# design.net
KiCad netlist of a schematic drawn in Altium Designer
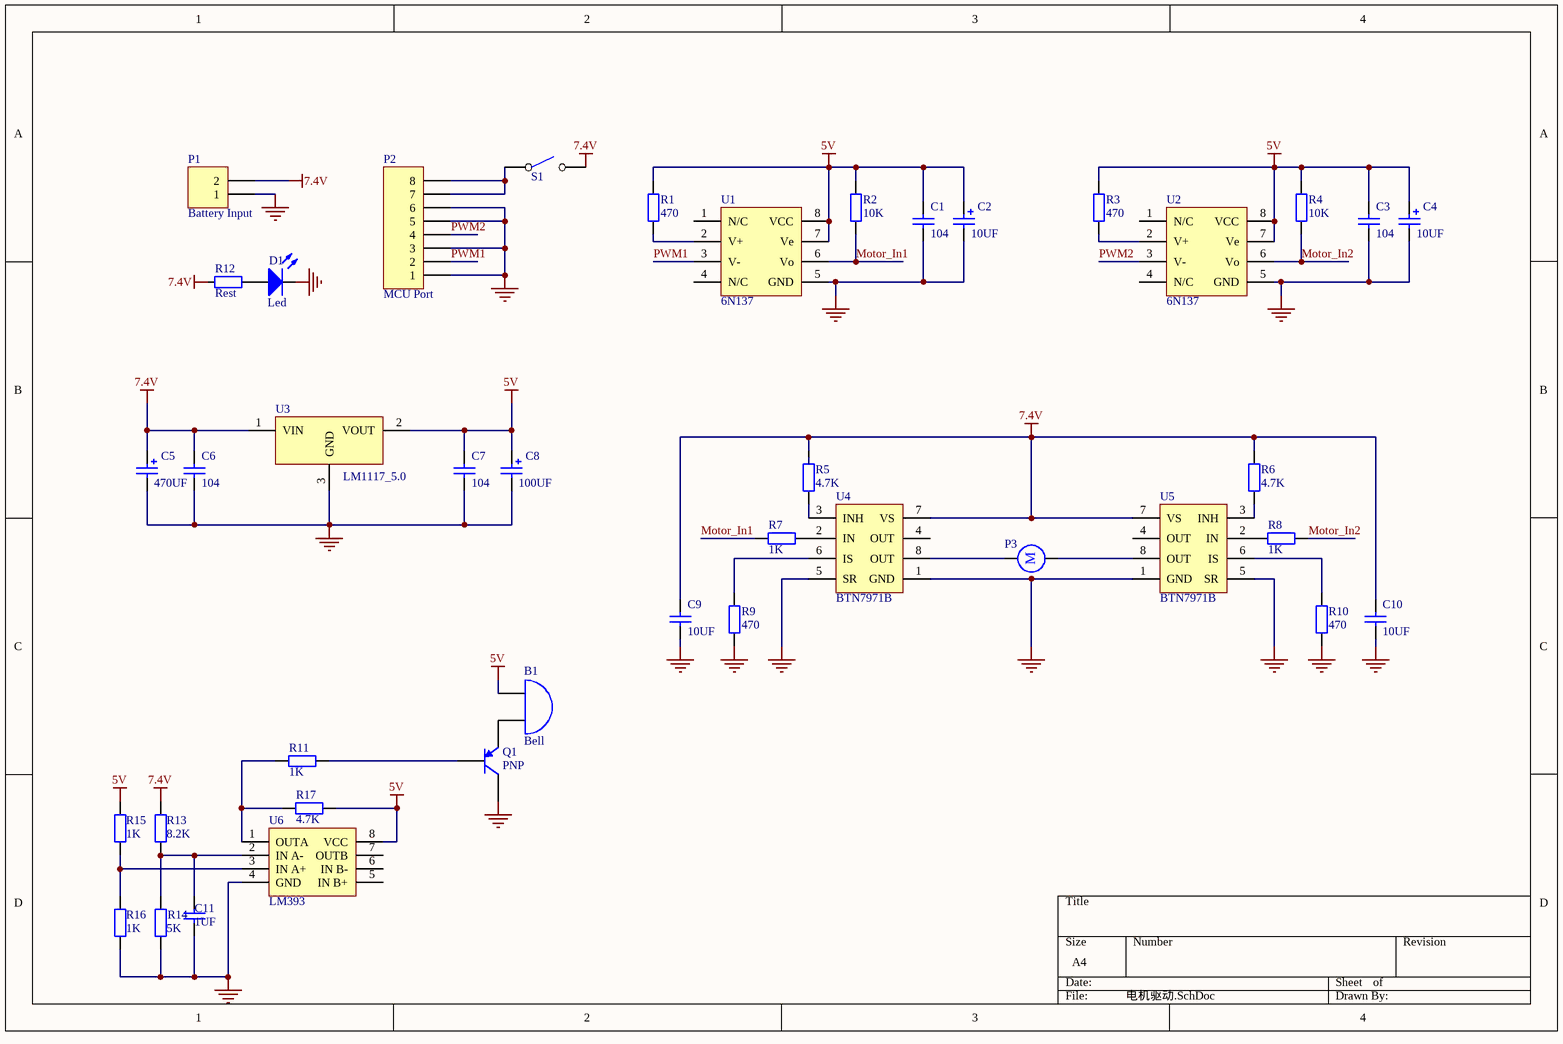
[diagram p0: 电机驱动.SchDoc]

(export (version "E")
  (design (tool "Eeschema 10.0.6"))
  (components
    (comp (ref "B1")
      (value "Bell")
      (footprint "Buzzer")
      (description "Electrical Bell")
      (fields (field (name "PUBLISHER") "Altium Limited"))
      (libsource (lib "Miscellaneous Devices") (part "Bell"))
    )
    (comp (ref "C1") (value "104") (footprint "0805") (libsource (lib "飞思卡尔") (part "Cap")))
    (comp (ref "C2")
      (value "10UF")
      (footprint "tiepian 100uf 6*7")
      (libsource (lib "飞思卡尔") (part "Cap Pol1"))
    )
    (comp (ref "C3") (value "104") (footprint "0805") (libsource (lib "飞思卡尔") (part "Cap")))
    (comp (ref "C4")
      (value "10UF")
      (footprint "tiepian 100uf 6*7")
      (libsource (lib "飞思卡尔") (part "Cap Pol1"))
    )
    (comp (ref "C5")
      (value "470UF")
      (footprint "tie pian 470uf 10*10.3")
      (libsource (lib "飞思卡尔") (part "Cap Pol1"))
    )
    (comp (ref "C6") (value "104") (footprint "0805") (libsource (lib "飞思卡尔") (part "Cap")))
    (comp (ref "C7") (value "104") (footprint "0805") (libsource (lib "飞思卡尔") (part "Cap")))
    (comp (ref "C8")
      (value "100UF")
      (footprint "tiepian 100uf 6*7")
      (libsource (lib "飞思卡尔") (part "Cap Pol1"))
    )
    (comp (ref "C9") (value "10UF") (footprint "7343") (libsource (lib "飞思卡尔") (part "Cap")))
    (comp (ref "C10") (value "10UF") (footprint "7343") (libsource (lib "飞思卡尔") (part "Cap")))
    (comp (ref "C11") (value "1UF") (footprint "0805") (libsource (lib "飞思卡尔") (part "Cap")))
    (comp (ref "D1") (value "Led") (footprint "0805") (libsource (lib "飞思卡尔") (part "Led")))
    (comp (ref "P1")
      (value "Battery Input")
      (footprint "XT-30")
      (description "Header, 2-Pin")
      (fields (field (name "PUBLISHER") "Altium Limited"))
      (libsource (lib "Miscellaneous Connectors") (part "Header 2"))
    )
    (comp (ref "P2")
      (value "MCU Port")
      (footprint "8P-2.54")
      (description "Header, 8-Pin")
      (fields (field (name "PUBLISHER") "Altium Limited"))
      (libsource (lib "Miscellaneous Connectors") (part "Header 8"))
    )
    (comp (ref "P3") (value "Motor") (footprint "接头10MM") (libsource (lib "飞思卡尔") (part "Motor")))
    (comp (ref "Q1")
      (value "PNP")
      (footprint "SOT-23")
      (description "PNP Bipolar Transistor")
      (fields (field (name "PUBLISHER") "Altium Limited"))
      (libsource (lib "Miscellaneous Devices") (part "PNP"))
    )
    (comp (ref "R1") (value "470") (footprint "0805") (libsource (lib "") (part "Rest_1")))
    (comp (ref "R2") (value "10K") (footprint "0805") (libsource (lib "") (part "Rest_1")))
    (comp (ref "R3") (value "470") (footprint "0805") (libsource (lib "") (part "Rest_1")))
    (comp (ref "R4") (value "10K") (footprint "0805") (libsource (lib "") (part "Rest_1")))
    (comp (ref "R5") (value "4.7K") (footprint "0805") (libsource (lib "") (part "Rest_1")))
    (comp (ref "R6") (value "4.7K") (footprint "0805") (libsource (lib "") (part "Rest_1")))
    (comp (ref "R7") (value "1K") (footprint "0805") (libsource (lib "飞思卡尔") (part "Rest")))
    (comp (ref "R8") (value "1K") (footprint "0805") (libsource (lib "飞思卡尔") (part "Rest")))
    (comp (ref "R9") (value "470") (footprint "0805") (libsource (lib "") (part "Rest_1")))
    (comp (ref "R10") (value "470") (footprint "0805") (libsource (lib "") (part "Rest_1")))
    (comp (ref "R11") (value "1K") (footprint "0805") (libsource (lib "飞思卡尔") (part "Rest")))
    (comp (ref "R12") (value "Rest") (footprint "0805") (libsource (lib "") (part "Rest_2")))
    (comp (ref "R13") (value "8.2K") (footprint "0805") (libsource (lib "") (part "Rest_1")))
    (comp (ref "R14") (value "5K") (footprint "0805") (libsource (lib "") (part "Rest_1")))
    (comp (ref "R15") (value "1K") (footprint "0805") (libsource (lib "") (part "Rest_1")))
    (comp (ref "R16") (value "1K") (footprint "0805") (libsource (lib "") (part "Rest_1")))
    (comp (ref "R17") (value "4.7K") (footprint "0805") (libsource (lib "飞思卡尔") (part "Rest")))
    (comp (ref "S1") (value "单刀开关") (footprint "钮子开关") (libsource (lib "按钮&开关") (part "单刀开关")))
    (comp (ref "U1") (value "6N137") (footprint "6N137") (libsource (lib "飞思卡尔") (part "6n137")))
    (comp (ref "U2") (value "6N137") (footprint "6N137") (libsource (lib "飞思卡尔") (part "6n137")))
    (comp (ref "U3") (value "LM1117_5.0") (footprint "SOT-223") (libsource (lib "飞思卡尔") (part "LM1117_5V")))
    (comp (ref "U4") (value "BTN7971B") (footprint "BTN7971B") (libsource (lib "飞思卡尔") (part "BTN7971B")))
    (comp (ref "U5") (value "BTN7971B") (footprint "BTN7971B") (libsource (lib "") (part "BTN7971B_1")))
    (comp (ref "U6") (value "LM393") (footprint "SOP-8") (libsource (lib "飞思卡尔") (part "LM393")))
  )
  (nets
    (net (code "1") (name "/Motor_In1") (class "Default")
      (node (ref "R2") (pin "1") (pinfunction "1_1") (pintype "passive"))
      (node (ref "R7") (pin "2") (pinfunction "2_2") (pintype "passive"))
      (node (ref "U1") (pin "6") (pinfunction "Vo_6") (pintype "passive"))
    )
    (net (code "2") (name "/Motor_In2") (class "Default")
      (node (ref "R4") (pin "1") (pinfunction "1_1") (pintype "passive"))
      (node (ref "R8") (pin "1") (pinfunction "1_1") (pintype "passive"))
      (node (ref "U2") (pin "6") (pinfunction "Vo_6") (pintype "passive"))
    )
    (net (code "3") (name "/PWM1") (class "Default")
      (node (ref "P2") (pin "2") (pinfunction "2_2") (pintype "passive"))
      (node (ref "U1") (pin "3") (pinfunction "V-_3") (pintype "passive"))
    )
    (net (code "4") (name "/PWM2") (class "Default")
      (node (ref "P2") (pin "4") (pinfunction "4_4") (pintype "passive"))
      (node (ref "U2") (pin "3") (pinfunction "V-_3") (pintype "passive"))
    )
    (net (code "5") (name "5V") (class "Default")
      (node (ref "B1") (pin "1") (pinfunction "A_1") (pintype "passive"))
      (node (ref "C1") (pin "2") (pinfunction "2_2") (pintype "passive"))
      (node (ref "C2") (pin "1") (pinfunction "1_1") (pintype "passive"))
      (node (ref "C3") (pin "2") (pinfunction "2_2") (pintype "passive"))
      (node (ref "C4") (pin "1") (pinfunction "1_1") (pintype "passive"))
      (node (ref "C7") (pin "2") (pinfunction "2_2") (pintype "passive"))
      (node (ref "C8") (pin "1") (pinfunction "1_1") (pintype "passive"))
      (node (ref "R1") (pin "2") (pinfunction "2_2") (pintype "passive"))
      (node (ref "R15") (pin "2") (pinfunction "2_2") (pintype "passive"))
      (node (ref "R17") (pin "1") (pinfunction "1_1") (pintype "passive"))
      (node (ref "R2") (pin "2") (pinfunction "2_2") (pintype "passive"))
      (node (ref "R3") (pin "2") (pinfunction "2_2") (pintype "passive"))
      (node (ref "R4") (pin "2") (pinfunction "2_2") (pintype "passive"))
      (node (ref "U1") (pin "7") (pinfunction "Ve_7") (pintype "passive"))
      (node (ref "U1") (pin "8") (pinfunction "VCC_8") (pintype "passive"))
      (node (ref "U2") (pin "7") (pinfunction "Ve_7") (pintype "passive"))
      (node (ref "U2") (pin "8") (pinfunction "VCC_8") (pintype "passive"))
      (node (ref "U3") (pin "2") (pinfunction "VOUT_2") (pintype "passive"))
      (node (ref "U6") (pin "8") (pinfunction "VCC_8") (pintype "passive"))
    )
    (net (code "6") (name "7.4V") (class "Default")
      (node (ref "C10") (pin "2") (pinfunction "2_2") (pintype "passive"))
      (node (ref "C5") (pin "1") (pinfunction "1_1") (pintype "passive"))
      (node (ref "C6") (pin "2") (pinfunction "2_2") (pintype "passive"))
      (node (ref "C9") (pin "2") (pinfunction "2_2") (pintype "passive"))
      (node (ref "P1") (pin "2") (pinfunction "2_2") (pintype "passive"))
      (node (ref "R13") (pin "2") (pinfunction "2_2") (pintype "passive"))
      (node (ref "R5") (pin "2") (pinfunction "2_2") (pintype "passive"))
      (node (ref "R6") (pin "2") (pinfunction "2_2") (pintype "passive"))
      (node (ref "S1") (pin "2") (pinfunction "2_2") (pintype "passive"))
      (node (ref "U3") (pin "1") (pinfunction "VIN_1") (pintype "passive"))
      (node (ref "U4") (pin "7") (pinfunction "VS_7") (pintype "passive"))
      (node (ref "U5") (pin "7") (pinfunction "VS_7") (pintype "passive"))
    )
    (net (code "7") (name "GND") (class "Default")
      (node (ref "C1") (pin "1") (pinfunction "1_1") (pintype "passive"))
      (node (ref "C10") (pin "1") (pinfunction "1_1") (pintype "passive"))
      (node (ref "C11") (pin "1") (pinfunction "1_1") (pintype "passive"))
      (node (ref "C2") (pin "2") (pinfunction "2_2") (pintype "passive"))
      (node (ref "C3") (pin "1") (pinfunction "1_1") (pintype "passive"))
      (node (ref "C4") (pin "2") (pinfunction "2_2") (pintype "passive"))
      (node (ref "C5") (pin "2") (pinfunction "2_2") (pintype "passive"))
      (node (ref "C6") (pin "1") (pinfunction "1_1") (pintype "passive"))
      (node (ref "C7") (pin "1") (pinfunction "1_1") (pintype "passive"))
      (node (ref "C8") (pin "2") (pinfunction "2_2") (pintype "passive"))
      (node (ref "C9") (pin "1") (pinfunction "1_1") (pintype "passive"))
      (node (ref "D1") (pin "2") (pinfunction "2_2") (pintype "passive"))
      (node (ref "P1") (pin "1") (pinfunction "1_1") (pintype "passive"))
      (node (ref "P2") (pin "1") (pinfunction "1_1") (pintype "passive"))
      (node (ref "P2") (pin "3") (pinfunction "3_3") (pintype "passive"))
      (node (ref "P2") (pin "5") (pinfunction "5_5") (pintype "passive"))
      (node (ref "P2") (pin "6") (pinfunction "6_6") (pintype "passive"))
      (node (ref "Q1") (pin "1") (pinfunction "C_1") (pintype "passive"))
      (node (ref "R10") (pin "1") (pinfunction "1_1") (pintype "passive"))
      (node (ref "R14") (pin "1") (pinfunction "1_1") (pintype "passive"))
      (node (ref "R16") (pin "1") (pinfunction "1_1") (pintype "passive"))
      (node (ref "R9") (pin "1") (pinfunction "1_1") (pintype "passive"))
      (node (ref "U1") (pin "5") (pinfunction "GND_5") (pintype "passive"))
      (node (ref "U2") (pin "5") (pinfunction "GND_5") (pintype "passive"))
      (node (ref "U3") (pin "3") (pinfunction "GND_3") (pintype "passive"))
      (node (ref "U4") (pin "1") (pinfunction "GND_1") (pintype "passive"))
      (node (ref "U4") (pin "5") (pinfunction "SR_5") (pintype "passive"))
      (node (ref "U5") (pin "1") (pinfunction "GND_1") (pintype "passive"))
      (node (ref "U5") (pin "5") (pinfunction "SR_5") (pintype "passive"))
      (node (ref "U6") (pin "4") (pinfunction "GND_4") (pintype "passive"))
    )
    (net (code "8") (name "Net-(B1-B)") (class "Default")
      (node (ref "B1") (pin "2") (pinfunction "B_2") (pintype "passive"))
      (node (ref "Q1") (pin "3") (pinfunction "E_3") (pintype "passive"))
    )
    (net (code "9") (name "Net-(D1-Pad1)") (class "Default")
      (node (ref "D1") (pin "1") (pinfunction "1_1") (pintype "passive"))
      (node (ref "R12") (pin "2") (pinfunction "2_2") (pintype "passive"))
    )
    (net (code "10") (name "Net-(P2-Pad7)") (class "Default")
      (node (ref "P2") (pin "7") (pinfunction "7_7") (pintype "passive"))
      (node (ref "P2") (pin "8") (pinfunction "8_8") (pintype "passive"))
      (node (ref "S1") (pin "1") (pinfunction "1_1") (pintype "passive"))
    )
    (net (code "11") (name "Net-(P3-Pad1)") (class "Default")
      (node (ref "P3") (pin "1") (pinfunction "1_1") (pintype "passive"))
      (node (ref "U4") (pin "8") (pinfunction "OUT_8") (pintype "passive"))
    )
    (net (code "12") (name "Net-(P3-Pad2)") (class "Default")
      (node (ref "P3") (pin "2") (pinfunction "2_2") (pintype "passive"))
      (node (ref "U5") (pin "8") (pinfunction "OUT_8") (pintype "passive"))
    )
    (net (code "13") (name "Net-(Q1-B)") (class "Default")
      (node (ref "Q1") (pin "2") (pinfunction "B_2") (pintype "passive"))
      (node (ref "R11") (pin "1") (pinfunction "1_1") (pintype "passive"))
    )
    (net (code "14") (name "Net-(U1-V+)") (class "Default")
      (node (ref "R1") (pin "1") (pinfunction "1_1") (pintype "passive"))
      (node (ref "U1") (pin "2") (pinfunction "V+_2") (pintype "passive"))
    )
    (net (code "15") (name "Net-(U2-V+)") (class "Default")
      (node (ref "R3") (pin "1") (pinfunction "1_1") (pintype "passive"))
      (node (ref "U2") (pin "2") (pinfunction "V+_2") (pintype "passive"))
    )
    (net (code "16") (name "Net-(U4-IN)") (class "Default")
      (node (ref "R7") (pin "1") (pinfunction "1_1") (pintype "passive"))
      (node (ref "U4") (pin "2") (pinfunction "IN_2") (pintype "passive"))
    )
    (net (code "17") (name "Net-(U4-INH)") (class "Default")
      (node (ref "R5") (pin "1") (pinfunction "1_1") (pintype "passive"))
      (node (ref "U4") (pin "3") (pinfunction "INH_3") (pintype "passive"))
    )
    (net (code "18") (name "Net-(U4-IS)") (class "Default")
      (node (ref "R9") (pin "2") (pinfunction "2_2") (pintype "passive"))
      (node (ref "U4") (pin "6") (pinfunction "IS_6") (pintype "passive"))
    )
    (net (code "19") (name "Net-(U5-IN)") (class "Default")
      (node (ref "R8") (pin "2") (pinfunction "2_2") (pintype "passive"))
      (node (ref "U5") (pin "2") (pinfunction "IN_2") (pintype "passive"))
    )
    (net (code "20") (name "Net-(U5-INH)") (class "Default")
      (node (ref "R6") (pin "1") (pinfunction "1_1") (pintype "passive"))
      (node (ref "U5") (pin "3") (pinfunction "INH_3") (pintype "passive"))
    )
    (net (code "21") (name "Net-(U5-IS)") (class "Default")
      (node (ref "R10") (pin "2") (pinfunction "2_2") (pintype "passive"))
      (node (ref "U5") (pin "6") (pinfunction "IS_6") (pintype "passive"))
    )
    (net (code "22") (name "Net-(U6-IN_A+)") (class "Default")
      (node (ref "R15") (pin "1") (pinfunction "1_1") (pintype "passive"))
      (node (ref "R16") (pin "2") (pinfunction "2_2") (pintype "passive"))
      (node (ref "U6") (pin "3") (pinfunction "IN_A+_3") (pintype "passive"))
    )
    (net (code "23") (name "Net-(U6-IN_A-)") (class "Default")
      (node (ref "C11") (pin "2") (pinfunction "2_2") (pintype "passive"))
      (node (ref "R13") (pin "1") (pinfunction "1_1") (pintype "passive"))
      (node (ref "R14") (pin "2") (pinfunction "2_2") (pintype "passive"))
      (node (ref "U6") (pin "2") (pinfunction "IN_A-_2") (pintype "passive"))
    )
    (net (code "24") (name "Net-(U6-OUTA)") (class "Default")
      (node (ref "R11") (pin "2") (pinfunction "2_2") (pintype "passive"))
      (node (ref "R17") (pin "2") (pinfunction "2_2") (pintype "passive"))
      (node (ref "U6") (pin "1") (pinfunction "OUTA_1") (pintype "passive"))
    )
    (net (code "25") (name "unconnected-(R12-Pad1)") (class "Default")
      (node (ref "R12") (pin "1") (pinfunction "1_1") (pintype "passive"))
    )
    (net (code "26") (name "unconnected-(U1-N{slash}C-Pad1)") (class "Default")
      (node (ref "U1") (pin "1") (pinfunction "N/C_1") (pintype "passive"))
    )
    (net (code "27") (name "unconnected-(U1-N{slash}C-Pad4)") (class "Default")
      (node (ref "U1") (pin "4") (pinfunction "N/C_4") (pintype "passive"))
    )
    (net (code "28") (name "unconnected-(U2-N{slash}C-Pad1)") (class "Default")
      (node (ref "U2") (pin "1") (pinfunction "N/C_1") (pintype "passive"))
    )
    (net (code "29") (name "unconnected-(U2-N{slash}C-Pad4)") (class "Default")
      (node (ref "U2") (pin "4") (pinfunction "N/C_4") (pintype "passive"))
    )
    (net (code "30") (name "unconnected-(U4-OUT-Pad4)") (class "Default")
      (node (ref "U4") (pin "4") (pinfunction "OUT_4") (pintype "passive"))
    )
    (net (code "31") (name "unconnected-(U5-OUT-Pad4)") (class "Default")
      (node (ref "U5") (pin "4") (pinfunction "OUT_4") (pintype "passive"))
    )
    (net (code "32") (name "unconnected-(U6-IN_B+-Pad5)") (class "Default")
      (node (ref "U6") (pin "5") (pinfunction "IN_B+_5") (pintype "passive"))
    )
    (net (code "33") (name "unconnected-(U6-IN_B--Pad6)") (class "Default")
      (node (ref "U6") (pin "6") (pinfunction "IN_B-_6") (pintype "passive"))
    )
    (net (code "34") (name "unconnected-(U6-OUTB-Pad7)") (class "Default")
      (node (ref "U6") (pin "7") (pinfunction "OUTB_7") (pintype "passive"))
    )
  )
)
